# Power.net
KiCad netlist of a schematic drawn in Altium Designer
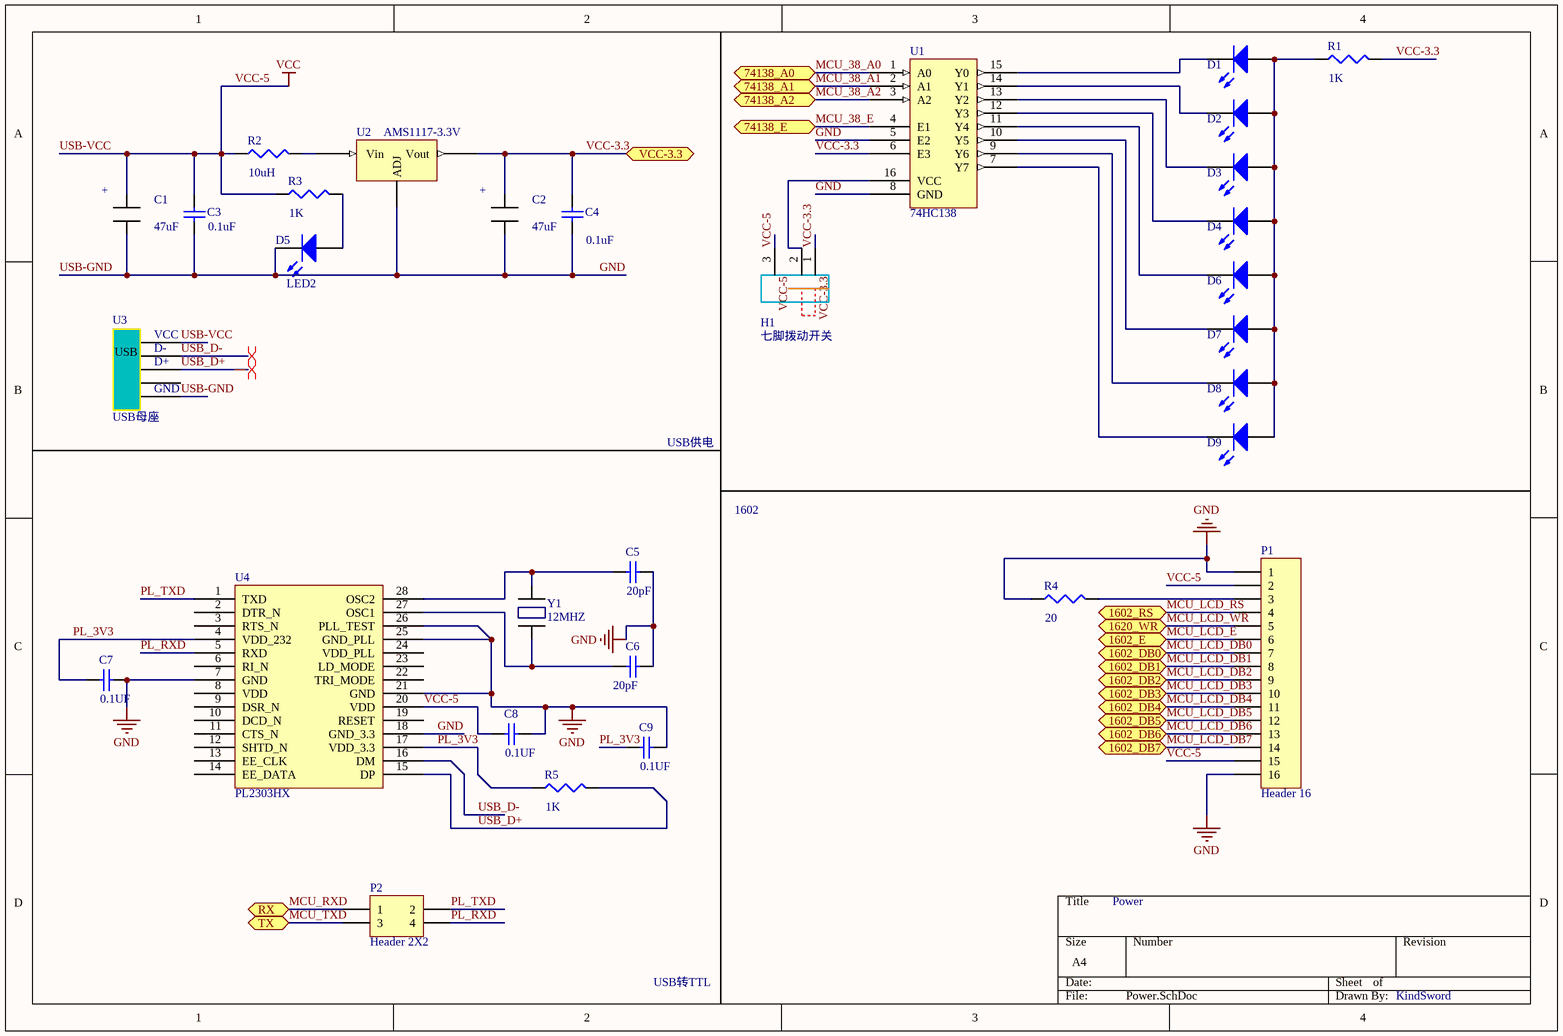
[diagram p0: Power.SchDoc]

(export (version "E")
  (design (tool "Eeschema 10.0.6"))
  (components
    (comp (ref "C1") (value "47uF") (footprint "A型坦电容") (libsource (lib "KindSword") (part "A型坦电容")))
    (comp (ref "C2") (value "47uF") (footprint "A型坦电容") (libsource (lib "KindSword") (part "A型坦电容")))
    (comp (ref "C3")
      (value "0.1uF")
      (footprint "C1206")
      (description "Capacitor (Semiconductor SIM Model)")
      (fields (field (name "Comment") "Cap Semi") (field (name "PUBLISHER") "Altium Limited"))
      (libsource (lib "Miscellaneous Devices") (part "Cap Semi"))
    )
    (comp (ref "C4")
      (value "0.1uF")
      (footprint "C1206")
      (description "Capacitor (Semiconductor SIM Model)")
      (fields (field (name "Comment") "Cap Semi") (field (name "PUBLISHER") "Altium Limited"))
      (libsource (lib "Miscellaneous Devices") (part "Cap Semi"))
    )
    (comp (ref "C5")
      (value "20pF")
      (footprint "C1206")
      (description "Capacitor (Semiconductor SIM Model)")
      (fields (field (name "Comment") "Cap Semi") (field (name "PUBLISHER") "Altium Limited"))
      (libsource (lib "Miscellaneous Devices") (part "Cap Semi"))
    )
    (comp (ref "C6")
      (value "20pF")
      (footprint "C1206")
      (description "Capacitor (Semiconductor SIM Model)")
      (fields (field (name "Comment") "Cap Semi") (field (name "PUBLISHER") "Altium Limited"))
      (libsource (lib "Miscellaneous Devices") (part "Cap Semi"))
    )
    (comp (ref "C7")
      (value "0.1UF")
      (footprint "C1206")
      (description "Capacitor (Semiconductor SIM Model)")
      (fields (field (name "Comment") "Cap Semi") (field (name "PUBLISHER") "Altium Limited"))
      (libsource (lib "Miscellaneous Devices") (part "Cap Semi"))
    )
    (comp (ref "C8")
      (value "0.1UF")
      (footprint "C1206")
      (description "Capacitor (Semiconductor SIM Model)")
      (fields (field (name "Comment") "Cap Semi") (field (name "PUBLISHER") "Altium Limited"))
      (libsource (lib "Miscellaneous Devices") (part "Cap Semi"))
    )
    (comp (ref "C9")
      (value "0.1UF")
      (footprint "C1206")
      (description "Capacitor (Semiconductor SIM Model)")
      (fields (field (name "Comment") "Cap Semi") (field (name "PUBLISHER") "Altium Limited"))
      (libsource (lib "Miscellaneous Devices") (part "Cap Semi"))
    )
    (comp (ref "D1")
      (value "LED2")
      (footprint "3.2X1.6X1.1")
      (description "Typical RED, GREEN, YELLOW, AMBER GaAs LED")
      (fields (field (name "PUBLISHER") "Altium Limited"))
      (libsource (lib "Miscellaneous Devices") (part "LED2"))
    )
    (comp (ref "D2")
      (value "LED2")
      (footprint "3.2X1.6X1.1")
      (description "Typical RED, GREEN, YELLOW, AMBER GaAs LED")
      (fields (field (name "PUBLISHER") "Altium Limited"))
      (libsource (lib "Miscellaneous Devices") (part "LED2"))
    )
    (comp (ref "D3")
      (value "LED2")
      (footprint "3.2X1.6X1.1")
      (description "Typical RED, GREEN, YELLOW, AMBER GaAs LED")
      (fields (field (name "PUBLISHER") "Altium Limited"))
      (libsource (lib "Miscellaneous Devices") (part "LED2"))
    )
    (comp (ref "D4")
      (value "LED2")
      (footprint "3.2X1.6X1.1")
      (description "Typical RED, GREEN, YELLOW, AMBER GaAs LED")
      (fields (field (name "PUBLISHER") "Altium Limited"))
      (libsource (lib "Miscellaneous Devices") (part "LED2"))
    )
    (comp (ref "D5")
      (value "LED2")
      (footprint "3.2X1.6X1.1")
      (description "Typical RED, GREEN, YELLOW, AMBER GaAs LED")
      (fields (field (name "PUBLISHER") "Altium Limited"))
      (libsource (lib "Miscellaneous Devices") (part "LED2"))
    )
    (comp (ref "D6")
      (value "LED1")
      (footprint "3.2X1.6X1.1")
      (description "Typical RED, GREEN, YELLOW, AMBER GaAs LED")
      (fields (field (name "PUBLISHER") "Altium Limited"))
      (libsource (lib "Miscellaneous Devices") (part "LED2"))
    )
    (comp (ref "D7")
      (value "LED2")
      (footprint "3.2X1.6X1.1")
      (description "Typical RED, GREEN, YELLOW, AMBER GaAs LED")
      (fields (field (name "PUBLISHER") "Altium Limited"))
      (libsource (lib "Miscellaneous Devices") (part "LED2"))
    )
    (comp (ref "D8")
      (value "LED2")
      (footprint "3.2X1.6X1.1")
      (description "Typical RED, GREEN, YELLOW, AMBER GaAs LED")
      (fields (field (name "PUBLISHER") "Altium Limited"))
      (libsource (lib "Miscellaneous Devices") (part "LED2"))
    )
    (comp (ref "D9")
      (value "LED2")
      (footprint "3.2X1.6X1.1")
      (description "Typical RED, GREEN, YELLOW, AMBER GaAs LED")
      (fields (field (name "PUBLISHER") "Altium Limited"))
      (libsource (lib "Miscellaneous Devices") (part "LED2"))
    )
    (comp (ref "H1")
      (value "七脚拨动开关")
      (footprint "七脚拨动开关")
      (description "H?")
      (libsource (lib "KindSword") (part "七脚拨动开关"))
    )
    (comp (ref "P1")
      (value "Header 16")
      (footprint "HDR1X16")
      (description "Header, 16-Pin")
      (fields (field (name "PUBLISHER") "Altium Limited"))
      (libsource (lib "Miscellaneous Connectors") (part "Header 16"))
    )
    (comp (ref "P2")
      (value "Header 2X2")
      (footprint "HDR2X2")
      (description "Header, 2-Pin, Dual row")
      (fields (field (name "PUBLISHER") "Altium Limited"))
      (libsource (lib "Miscellaneous Connectors") (part "Header 2X2"))
    )
    (comp (ref "R1")
      (value "1K")
      (footprint "14-1210")
      (description "Resistor")
      (fields (field (name "Comment") "Res3") (field (name "PUBLISHER") "Altium Limited"))
      (libsource (lib "Miscellaneous Devices") (part "Res3"))
    )
    (comp (ref "R2")
      (value "10uH")
      (footprint "14-1210")
      (description "Resistor")
      (fields (field (name "Comment") "Res3") (field (name "PUBLISHER") "Altium Limited"))
      (libsource (lib "Miscellaneous Devices") (part "Res3"))
    )
    (comp (ref "R3")
      (value "1K")
      (footprint "14-1210")
      (description "Resistor")
      (fields (field (name "Comment") "Res3") (field (name "PUBLISHER") "Altium Limited"))
      (libsource (lib "Miscellaneous Devices") (part "Res3"))
    )
    (comp (ref "R4")
      (value "20")
      (footprint "14-1210")
      (description "Resistor")
      (fields (field (name "Comment") "Res3") (field (name "PUBLISHER") "Altium Limited"))
      (libsource (lib "Miscellaneous Devices") (part "Res3"))
    )
    (comp (ref "R5")
      (value "1K")
      (footprint "14-1210")
      (description "Resistor")
      (fields (field (name "Comment") "Res3") (field (name "PUBLISHER") "Altium Limited"))
      (libsource (lib "Miscellaneous Devices") (part "Res3"))
    )
    (comp (ref "U1") (value "74HC138") (footprint "74HC138") (libsource (lib "KindSword") (part "74HC138")))
    (comp (ref "U2")
      (value "AMS1117-3.3V")
      (footprint "AMS1117")
      (libsource (lib "KindSword") (part "AMS1117"))
    )
    (comp (ref "U3")
      (value "USB母座")
      (footprint "MicroUSB母座")
      (description "U?")
      (libsource (lib "AD元件库") (part "MicroUSB母座"))
    )
    (comp (ref "U4")
      (value "PL2303HX")
      (footprint "PL2303HX")
      (libsource (lib "KindSword") (part "PL2303HX"))
    )
    (comp (ref "Y1")
      (value "12MHZ")
      (footprint "晶振")
      (description "Y?")
      (libsource (lib "KindSword") (part "晶振"))
    )
  )
  (nets
    (net (code "1") (name "/MCU_38_A0") (class "Default")
      (node (ref "U1") (pin "1") (pinfunction "A0_1") (pintype "input"))
    )
    (net (code "2") (name "/MCU_38_A1") (class "Default")
      (node (ref "U1") (pin "2") (pinfunction "A1_2") (pintype "input"))
    )
    (net (code "3") (name "/MCU_38_A2") (class "Default")
      (node (ref "U1") (pin "3") (pinfunction "A2_3") (pintype "input"))
    )
    (net (code "4") (name "/MCU_38_E") (class "Default")
      (node (ref "U1") (pin "4") (pinfunction "E1_4") (pintype "passive"))
    )
    (net (code "5") (name "/MCU_LCD_DB0") (class "Default")
      (node (ref "P1") (pin "7") (pinfunction "7_7") (pintype "passive"))
    )
    (net (code "6") (name "/MCU_LCD_DB1") (class "Default")
      (node (ref "P1") (pin "8") (pinfunction "8_8") (pintype "passive"))
    )
    (net (code "7") (name "/MCU_LCD_DB2") (class "Default")
      (node (ref "P1") (pin "9") (pinfunction "9_9") (pintype "passive"))
    )
    (net (code "8") (name "/MCU_LCD_DB3") (class "Default")
      (node (ref "P1") (pin "10") (pinfunction "10_10") (pintype "passive"))
    )
    (net (code "9") (name "/MCU_LCD_DB4") (class "Default")
      (node (ref "P1") (pin "11") (pinfunction "11_11") (pintype "passive"))
    )
    (net (code "10") (name "/MCU_LCD_DB5") (class "Default")
      (node (ref "P1") (pin "12") (pinfunction "12_12") (pintype "passive"))
    )
    (net (code "11") (name "/MCU_LCD_DB6") (class "Default")
      (node (ref "P1") (pin "13") (pinfunction "13_13") (pintype "passive"))
    )
    (net (code "12") (name "/MCU_LCD_DB7") (class "Default")
      (node (ref "P1") (pin "14") (pinfunction "14_14") (pintype "passive"))
    )
    (net (code "13") (name "/MCU_LCD_E") (class "Default")
      (node (ref "P1") (pin "6") (pinfunction "6_6") (pintype "passive"))
    )
    (net (code "14") (name "/MCU_LCD_RS") (class "Default")
      (node (ref "P1") (pin "4") (pinfunction "4_4") (pintype "passive"))
    )
    (net (code "15") (name "/MCU_LCD_WR") (class "Default")
      (node (ref "P1") (pin "5") (pinfunction "5_5") (pintype "passive"))
    )
    (net (code "16") (name "/MCU_RXD") (class "Default")
      (node (ref "P2") (pin "1") (pinfunction "1_1") (pintype "passive"))
    )
    (net (code "17") (name "/MCU_TXD") (class "Default")
      (node (ref "P2") (pin "3") (pinfunction "3_3") (pintype "passive"))
    )
    (net (code "18") (name "/PL_3V3") (class "Default")
      (node (ref "C7") (pin "1") (pinfunction "1_1") (pintype "passive"))
      (node (ref "C9") (pin "1") (pinfunction "1_1") (pintype "passive"))
      (node (ref "R5") (pin "1") (pinfunction "1_1") (pintype "passive"))
      (node (ref "U4") (pin "17") (pinfunction "VDD_3.3_17") (pintype "passive"))
      (node (ref "U4") (pin "4") (pinfunction "VDD_232_4") (pintype "passive"))
    )
    (net (code "19") (name "/PL_RXD") (class "Default")
      (node (ref "P2") (pin "4") (pinfunction "4_4") (pintype "passive"))
      (node (ref "U4") (pin "5") (pinfunction "RXD_5") (pintype "passive"))
    )
    (net (code "20") (name "/PL_TXD") (class "Default")
      (node (ref "P2") (pin "2") (pinfunction "2_2") (pintype "passive"))
      (node (ref "U4") (pin "1") (pinfunction "TXD_1") (pintype "passive"))
    )
    (net (code "21") (name "/USB_D+") (class "Default")
      (node (ref "R5") (pin "2") (pinfunction "2_2") (pintype "passive"))
      (node (ref "U3") (pin "3") (pintype "passive"))
      (node (ref "U4") (pin "15") (pinfunction "DP_15") (pintype "passive"))
    )
    (net (code "22") (name "/USB_D-") (class "Default")
      (node (ref "U3") (pin "2") (pintype "passive"))
      (node (ref "U4") (pin "16") (pinfunction "DM_16") (pintype "passive"))
    )
    (net (code "23") (name "/VCC-3.3") (class "Default")
      (node (ref "C2") (pin "2") (pinfunction "+_2") (pintype "passive"))
      (node (ref "C4") (pin "2") (pinfunction "2_2") (pintype "passive"))
      (node (ref "H1") (pin "1") (pinfunction "3_1") (pintype "passive"))
      (node (ref "R1") (pin "2") (pinfunction "2_2") (pintype "passive"))
      (node (ref "U1") (pin "6") (pinfunction "E3_6") (pintype "passive"))
      (node (ref "U2") (pin "2") (pinfunction "Vout_2") (pintype "output"))
    )
    (net (code "24") (name "GND") (class "Default")
      (node (ref "C1") (pin "1") (pinfunction "-_1") (pintype "passive"))
      (node (ref "C2") (pin "1") (pinfunction "-_1") (pintype "passive"))
      (node (ref "C3") (pin "1") (pinfunction "1_1") (pintype "passive"))
      (node (ref "C4") (pin "1") (pinfunction "1_1") (pintype "passive"))
      (node (ref "C5") (pin "2") (pinfunction "2_2") (pintype "passive"))
      (node (ref "C6") (pin "2") (pinfunction "2_2") (pintype "passive"))
      (node (ref "C7") (pin "2") (pinfunction "2_2") (pintype "passive"))
      (node (ref "C8") (pin "2") (pinfunction "2_2") (pintype "passive"))
      (node (ref "C9") (pin "2") (pinfunction "2_2") (pintype "passive"))
      (node (ref "D5") (pin "2") (pinfunction "K_2") (pintype "passive"))
      (node (ref "P1") (pin "1") (pinfunction "1_1") (pintype "passive"))
      (node (ref "P1") (pin "16") (pinfunction "16_16") (pintype "passive"))
      (node (ref "R4") (pin "1") (pinfunction "1_1") (pintype "passive"))
      (node (ref "U1") (pin "5") (pinfunction "E2_5") (pintype "passive"))
      (node (ref "U1") (pin "8") (pinfunction "GND_8") (pintype "power_in"))
      (node (ref "U2") (pin "1") (pinfunction "ADJ_1") (pintype "passive"))
      (node (ref "U3") (pin "5") (pintype "passive"))
      (node (ref "U4") (pin "18") (pinfunction "GND_3.3_18") (pintype "passive"))
      (node (ref "U4") (pin "21") (pinfunction "GND_21") (pintype "passive"))
      (node (ref "U4") (pin "25") (pinfunction "GND_PLL_25") (pintype "passive"))
      (node (ref "U4") (pin "26") (pinfunction "PLL_TEST_26") (pintype "passive"))
      (node (ref "U4") (pin "7") (pinfunction "GND_7") (pintype "passive"))
    )
    (net (code "25") (name "Net-(D1-A)") (class "Default")
      (node (ref "D1") (pin "1") (pinfunction "A_1") (pintype "passive"))
      (node (ref "D2") (pin "1") (pinfunction "A_1") (pintype "passive"))
      (node (ref "D3") (pin "1") (pinfunction "A_1") (pintype "passive"))
      (node (ref "D4") (pin "1") (pinfunction "A_1") (pintype "passive"))
      (node (ref "D6") (pin "1") (pinfunction "A_1") (pintype "passive"))
      (node (ref "D7") (pin "1") (pinfunction "A_1") (pintype "passive"))
      (node (ref "D8") (pin "1") (pinfunction "A_1") (pintype "passive"))
      (node (ref "D9") (pin "1") (pinfunction "A_1") (pintype "passive"))
      (node (ref "R1") (pin "1") (pinfunction "1_1") (pintype "passive"))
    )
    (net (code "26") (name "Net-(D1-K)") (class "Default")
      (node (ref "D1") (pin "2") (pinfunction "K_2") (pintype "passive"))
      (node (ref "U1") (pin "15") (pinfunction "Y0_15") (pintype "output"))
    )
    (net (code "27") (name "Net-(D2-K)") (class "Default")
      (node (ref "D2") (pin "2") (pinfunction "K_2") (pintype "passive"))
      (node (ref "U1") (pin "14") (pinfunction "Y1_14") (pintype "output"))
    )
    (net (code "28") (name "Net-(D3-K)") (class "Default")
      (node (ref "D3") (pin "2") (pinfunction "K_2") (pintype "passive"))
      (node (ref "U1") (pin "13") (pinfunction "Y2_13") (pintype "output"))
    )
    (net (code "29") (name "Net-(D4-K)") (class "Default")
      (node (ref "D4") (pin "2") (pinfunction "K_2") (pintype "passive"))
      (node (ref "U1") (pin "12") (pinfunction "Y3_12") (pintype "output"))
    )
    (net (code "30") (name "Net-(D5-A)") (class "Default")
      (node (ref "D5") (pin "1") (pinfunction "A_1") (pintype "passive"))
      (node (ref "R3") (pin "2") (pinfunction "2_2") (pintype "passive"))
    )
    (net (code "31") (name "Net-(D6-K)") (class "Default")
      (node (ref "D6") (pin "2") (pinfunction "K_2") (pintype "passive"))
      (node (ref "U1") (pin "11") (pinfunction "Y4_11") (pintype "output"))
    )
    (net (code "32") (name "Net-(D7-K)") (class "Default")
      (node (ref "D7") (pin "2") (pinfunction "K_2") (pintype "passive"))
      (node (ref "U1") (pin "10") (pinfunction "Y5_10") (pintype "output"))
    )
    (net (code "33") (name "Net-(D8-K)") (class "Default")
      (node (ref "D8") (pin "2") (pinfunction "K_2") (pintype "passive"))
      (node (ref "U1") (pin "9") (pinfunction "Y6_9") (pintype "output"))
    )
    (net (code "34") (name "Net-(D9-K)") (class "Default")
      (node (ref "D9") (pin "2") (pinfunction "K_2") (pintype "passive"))
      (node (ref "U1") (pin "7") (pinfunction "Y7_7") (pintype "output"))
    )
    (net (code "35") (name "Net-(H1-4)") (class "Default")
      (node (ref "H1") (pin "2") (pinfunction "4_2") (pintype "passive"))
      (node (ref "U1") (pin "16") (pinfunction "VCC_16") (pintype "power_in"))
    )
    (net (code "36") (name "Net-(P1-Pad3)") (class "Default")
      (node (ref "P1") (pin "3") (pinfunction "3_3") (pintype "passive"))
      (node (ref "R4") (pin "2") (pinfunction "2_2") (pintype "passive"))
    )
    (net (code "37") (name "Net-(U2-Vin)") (class "Default")
      (node (ref "R2") (pin "2") (pinfunction "2_2") (pintype "passive"))
      (node (ref "U2") (pin "3") (pinfunction "Vin_3") (pintype "input"))
    )
    (net (code "38") (name "Net-(U4-OSC1)") (class "Default")
      (node (ref "C6") (pin "1") (pinfunction "1_1") (pintype "passive"))
      (node (ref "U4") (pin "27") (pinfunction "OSC1_27") (pintype "passive"))
      (node (ref "Y1") (pin "1") (pintype "passive"))
    )
    (net (code "39") (name "Net-(U4-OSC2)") (class "Default")
      (node (ref "C5") (pin "1") (pinfunction "1_1") (pintype "passive"))
      (node (ref "U4") (pin "28") (pinfunction "OSC2_28") (pintype "passive"))
      (node (ref "Y1") (pin "2") (pintype "passive"))
    )
    (net (code "40") (name "VCC") (class "Default")
      (node (ref "C1") (pin "2") (pinfunction "+_2") (pintype "passive"))
      (node (ref "C3") (pin "2") (pinfunction "2_2") (pintype "passive"))
      (node (ref "C8") (pin "1") (pinfunction "1_1") (pintype "passive"))
      (node (ref "H1") (pin "3") (pinfunction "5_3") (pintype "passive"))
      (node (ref "P1") (pin "15") (pinfunction "15_15") (pintype "passive"))
      (node (ref "P1") (pin "2") (pinfunction "2_2") (pintype "passive"))
      (node (ref "R2") (pin "1") (pinfunction "1_1") (pintype "passive"))
      (node (ref "R3") (pin "1") (pinfunction "1_1") (pintype "passive"))
      (node (ref "U3") (pin "1") (pintype "passive"))
      (node (ref "U4") (pin "20") (pinfunction "VDD_20") (pintype "passive"))
    )
    (net (code "41") (name "unconnected-(U3-Pad4)") (class "Default")
      (node (ref "U3") (pin "4") (pintype "passive"))
    )
    (net (code "42") (name "unconnected-(U4-CTS_N-Pad11)") (class "Default")
      (node (ref "U4") (pin "11") (pinfunction "CTS_N_11") (pintype "passive"))
    )
    (net (code "43") (name "unconnected-(U4-DCD_N-Pad10)") (class "Default")
      (node (ref "U4") (pin "10") (pinfunction "DCD_N_10") (pintype "passive"))
    )
    (net (code "44") (name "unconnected-(U4-DSR_N-Pad9)") (class "Default")
      (node (ref "U4") (pin "9") (pinfunction "DSR_N_9") (pintype "passive"))
    )
    (net (code "45") (name "unconnected-(U4-DTR_N-Pad2)") (class "Default")
      (node (ref "U4") (pin "2") (pinfunction "DTR_N_2") (pintype "passive"))
    )
    (net (code "46") (name "unconnected-(U4-EE_CLK-Pad13)") (class "Default")
      (node (ref "U4") (pin "13") (pinfunction "EE_CLK_13") (pintype "passive"))
    )
    (net (code "47") (name "unconnected-(U4-EE_DATA-Pad14)") (class "Default")
      (node (ref "U4") (pin "14") (pinfunction "EE_DATA_14") (pintype "passive"))
    )
    (net (code "48") (name "unconnected-(U4-LD_MODE-Pad23)") (class "Default")
      (node (ref "U4") (pin "23") (pinfunction "LD_MODE_23") (pintype "passive"))
    )
    (net (code "49") (name "unconnected-(U4-RESET-Pad19)") (class "Default")
      (node (ref "U4") (pin "19") (pinfunction "RESET_19") (pintype "passive"))
    )
    (net (code "50") (name "unconnected-(U4-RI_N-Pad6)") (class "Default")
      (node (ref "U4") (pin "6") (pinfunction "RI_N_6") (pintype "passive"))
    )
    (net (code "51") (name "unconnected-(U4-RTS_N-Pad3)") (class "Default")
      (node (ref "U4") (pin "3") (pinfunction "RTS_N_3") (pintype "passive"))
    )
    (net (code "52") (name "unconnected-(U4-SHTD_N-Pad12)") (class "Default")
      (node (ref "U4") (pin "12") (pinfunction "SHTD_N_12") (pintype "passive"))
    )
    (net (code "53") (name "unconnected-(U4-TRI_MODE-Pad22)") (class "Default")
      (node (ref "U4") (pin "22") (pinfunction "TRI_MODE_22") (pintype "passive"))
    )
    (net (code "54") (name "unconnected-(U4-VDD-Pad8)") (class "Default")
      (node (ref "U4") (pin "8") (pinfunction "VDD_8") (pintype "passive"))
    )
    (net (code "55") (name "unconnected-(U4-VDD_PLL-Pad24)") (class "Default")
      (node (ref "U4") (pin "24") (pinfunction "VDD_PLL_24") (pintype "passive"))
    )
  )
)
